# sdr_3157.net
KiCad netlist of a schematic drawn in EAGLE
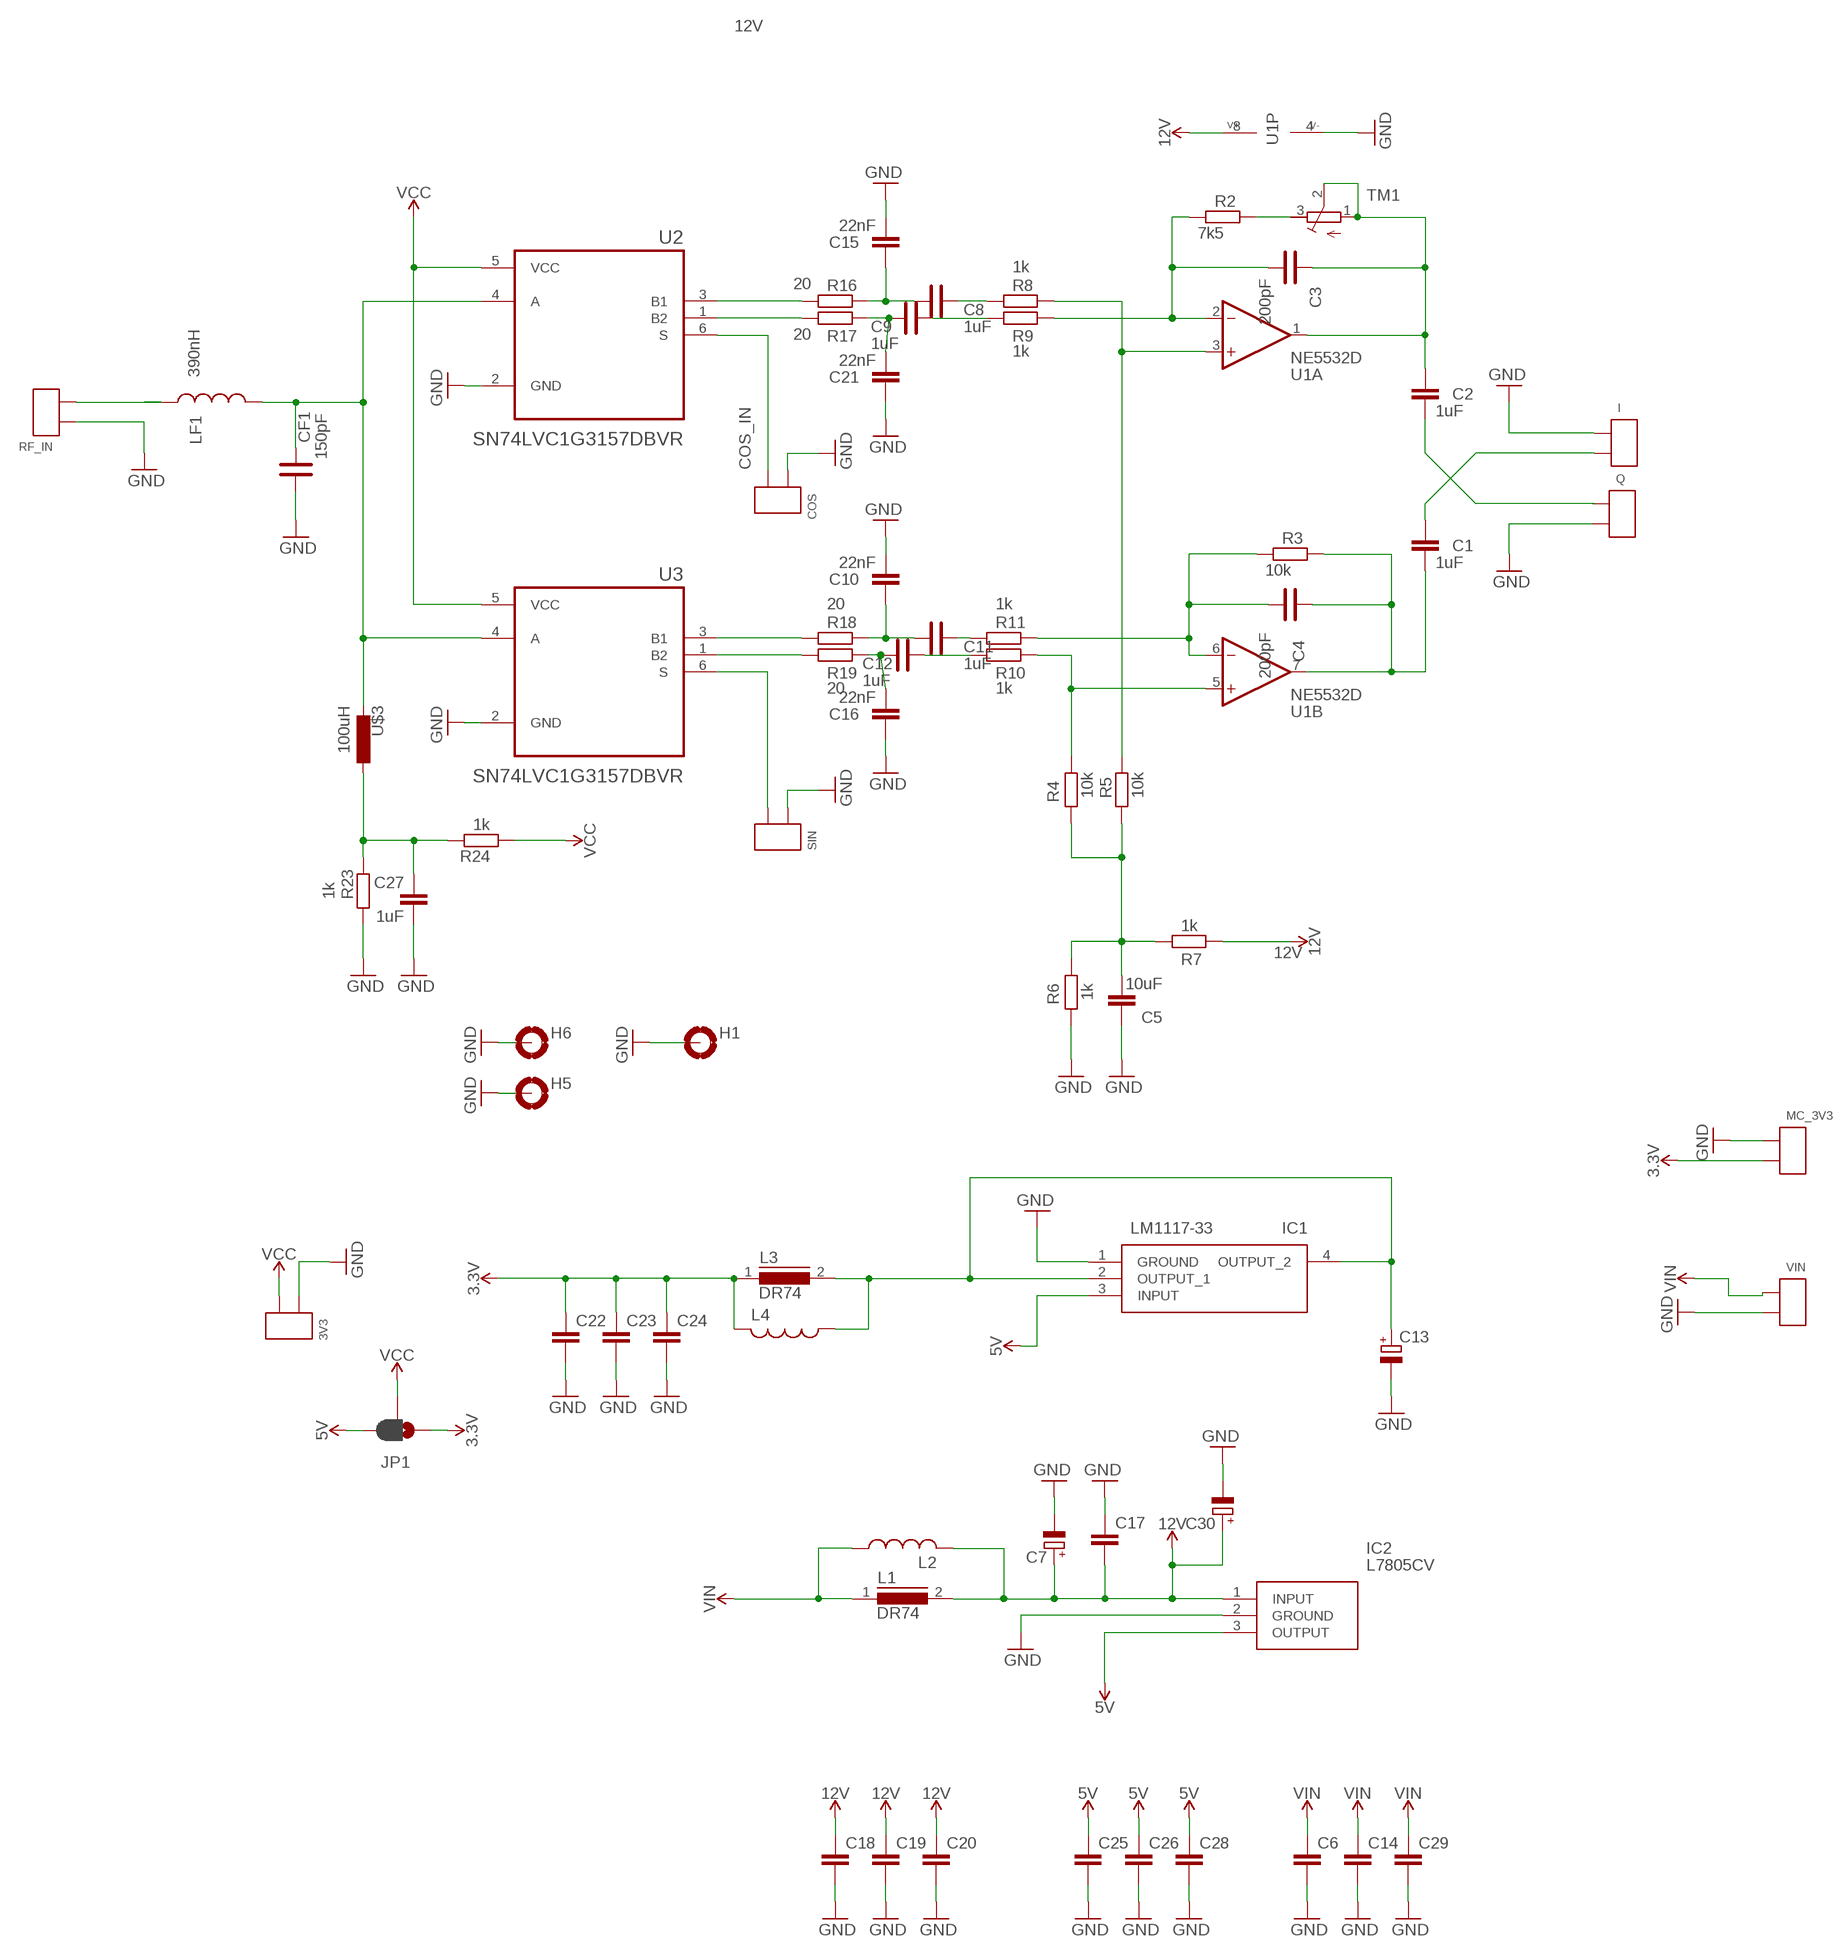
[diagram p0: schematic, sheet 1]

(export (version "E")
  (design (tool "Eeschema 10.0.6"))
  (components
    (comp (ref "3V3")
      (value "2X_SMD_PTH_PIN")
      (footprint "eagle-import:2X_SMD_PTH")
      (libsource (lib "eagle-import") (part "2X_SMD_PTH_PIN"))
    )
    (comp (ref "C1")
      (value "1uF")
      (footprint "eagle-import:C050-045X075")
      (libsource (lib "eagle-import") (part "C-EU050-045X075"))
    )
    (comp (ref "C2")
      (value "1uF")
      (footprint "eagle-import:C050-045X075")
      (libsource (lib "eagle-import") (part "C-EU050-045X075"))
    )
    (comp (ref "C3")
      (value "200pF")
      (footprint "eagle-import:C0805K")
      (libsource (lib "eagle-import") (part "C_0805_PTH"))
    )
    (comp (ref "C4")
      (value "200pF")
      (footprint "eagle-import:C0805K")
      (libsource (lib "eagle-import") (part "C_0805_PTH"))
    )
    (comp (ref "C5")
      (value "10uF")
      (footprint "eagle-import:C0805")
      (libsource (lib "eagle-import") (part "C_0805_SMD"))
    )
    (comp (ref "C6")
      (value "C_0805_SMD")
      (footprint "eagle-import:C0805")
      (libsource (lib "eagle-import") (part "C_0805_SMD"))
    )
    (comp (ref "C7")
      (value "C_POL")
      (footprint "eagle-import:E5-5")
      (libsource (lib "eagle-import") (part "C_POL"))
    )
    (comp (ref "C8")
      (value "1uF")
      (footprint "eagle-import:C0805K")
      (libsource (lib "eagle-import") (part "C_0805_PTH"))
    )
    (comp (ref "C9")
      (value "1uF")
      (footprint "eagle-import:C0805K")
      (libsource (lib "eagle-import") (part "C_0805_PTH"))
    )
    (comp (ref "C10")
      (value "22nF")
      (footprint "eagle-import:C0805")
      (libsource (lib "eagle-import") (part "C_0805_SMD"))
    )
    (comp (ref "C11")
      (value "1uF")
      (footprint "eagle-import:C0805K")
      (libsource (lib "eagle-import") (part "C_0805_PTH"))
    )
    (comp (ref "C12")
      (value "1uF")
      (footprint "eagle-import:C0805K")
      (libsource (lib "eagle-import") (part "C_0805_PTH"))
    )
    (comp (ref "C13")
      (value "C_POL")
      (footprint "eagle-import:E5-5")
      (libsource (lib "eagle-import") (part "C_POL"))
    )
    (comp (ref "C14")
      (value "C_0805_SMD")
      (footprint "eagle-import:C0805")
      (libsource (lib "eagle-import") (part "C_0805_SMD"))
    )
    (comp (ref "C15")
      (value "22nF")
      (footprint "eagle-import:C0805")
      (libsource (lib "eagle-import") (part "C_0805_SMD"))
    )
    (comp (ref "C16")
      (value "22nF")
      (footprint "eagle-import:C0805")
      (libsource (lib "eagle-import") (part "C_0805_SMD"))
    )
    (comp (ref "C17")
      (value "C_0805_SMD")
      (footprint "eagle-import:C0805")
      (libsource (lib "eagle-import") (part "C_0805_SMD"))
    )
    (comp (ref "C18")
      (value "C_0805_SMD")
      (footprint "eagle-import:C0805")
      (libsource (lib "eagle-import") (part "C_0805_SMD"))
    )
    (comp (ref "C19")
      (value "C_0805_SMD")
      (footprint "eagle-import:C0805")
      (libsource (lib "eagle-import") (part "C_0805_SMD"))
    )
    (comp (ref "C20")
      (value "C_0805_SMD")
      (footprint "eagle-import:C0805")
      (libsource (lib "eagle-import") (part "C_0805_SMD"))
    )
    (comp (ref "C21")
      (value "22nF")
      (footprint "eagle-import:C0805")
      (libsource (lib "eagle-import") (part "C_0805_SMD"))
    )
    (comp (ref "C22")
      (value "C_0805_SMD")
      (footprint "eagle-import:C0805")
      (libsource (lib "eagle-import") (part "C_0805_SMD"))
    )
    (comp (ref "C23")
      (value "C_0805_SMD")
      (footprint "eagle-import:C0805")
      (libsource (lib "eagle-import") (part "C_0805_SMD"))
    )
    (comp (ref "C24")
      (value "C_0805_SMD")
      (footprint "eagle-import:C0805")
      (libsource (lib "eagle-import") (part "C_0805_SMD"))
    )
    (comp (ref "C25")
      (value "C_0805_SMD")
      (footprint "eagle-import:C0805")
      (libsource (lib "eagle-import") (part "C_0805_SMD"))
    )
    (comp (ref "C26")
      (value "C_0805_SMD")
      (footprint "eagle-import:C0805")
      (libsource (lib "eagle-import") (part "C_0805_SMD"))
    )
    (comp (ref "C27")
      (value "1uF")
      (footprint "eagle-import:C0805")
      (libsource (lib "eagle-import") (part "C_0805_SMD"))
    )
    (comp (ref "C28")
      (value "C_0805_SMD")
      (footprint "eagle-import:C0805")
      (libsource (lib "eagle-import") (part "C_0805_SMD"))
    )
    (comp (ref "C29")
      (value "C_0805_SMD")
      (footprint "eagle-import:C0805")
      (libsource (lib "eagle-import") (part "C_0805_SMD"))
    )
    (comp (ref "C30")
      (value "C_POL")
      (footprint "eagle-import:E5-5")
      (libsource (lib "eagle-import") (part "C_POL"))
    )
    (comp (ref "CF1")
      (value "150pF")
      (footprint "eagle-import:C0805K")
      (libsource (lib "eagle-import") (part "C_0805_PTH"))
    )
    (comp (ref "COS")
      (value "2X_SMD_PTH_PIN")
      (footprint "eagle-import:2X_SMD_PTH")
      (libsource (lib "eagle-import") (part "2X_SMD_PTH_PIN"))
    )
    (comp (ref "H1")
      (value "MOUNT-PAD-ROUND3.0")
      (footprint "eagle-import:3,0-PAD")
      (libsource (lib "eagle-import") (part "MOUNT-PAD-ROUND3.0"))
    )
    (comp (ref "H5")
      (value "MOUNT-PAD-ROUND3.0")
      (footprint "eagle-import:3,0-PAD")
      (libsource (lib "eagle-import") (part "MOUNT-PAD-ROUND3.0"))
    )
    (comp (ref "H6")
      (value "MOUNT-PAD-ROUND3.0")
      (footprint "eagle-import:3,0-PAD")
      (libsource (lib "eagle-import") (part "MOUNT-PAD-ROUND3.0"))
    )
    (comp (ref "I")
      (value "2X_SMD_PTH_PIN")
      (footprint "eagle-import:2X_SMD_PTH")
      (libsource (lib "eagle-import") (part "2X_SMD_PTH_PIN"))
    )
    (comp (ref "IC1")
      (value "LM1117-33")
      (footprint "eagle-import:SOT230P700X180-4N")
      (fields
        (field (name "ARROW_PART_NUMBER") "LM1117MPX-33NOPB")
        (field (name "MOUSER_PART_NUMBER") "863-LM1117MPX-33NOPB")
      )
      (libsource (lib "eagle-import") (part "LM1117MPX-33NOPB"))
    )
    (comp (ref "IC2")
      (value "L7805CV")
      (footprint "eagle-import:TO255P460X1020X2008-3P")
      (fields (field (name "MOUSER_PART_NUMBER") "511-L7805CV"))
      (libsource (lib "eagle-import") (part "L7805CV"))
    )
    (comp (ref "JP1")
      (value "JUMPER-SMT_3_1-NC_PASTE_NO-SILK")
      (footprint "eagle-import:SMT-JUMPER_3_1-NC_PASTE_NO-SILK")
      (libsource (lib "eagle-import") (part "JUMPER-SMT_3_1-NC_PASTE_NO-SILK"))
    )
    (comp (ref "L1")
      (value "DR74")
      (footprint "eagle-import:DR74")
      (libsource (lib "eagle-import") (part "DR74"))
    )
    (comp (ref "L2")
      (value "L_0805_PTH")
      (footprint "eagle-import:M0805")
      (libsource (lib "eagle-import") (part "L_0805_PTH"))
    )
    (comp (ref "L3")
      (value "DR74")
      (footprint "eagle-import:DR74")
      (libsource (lib "eagle-import") (part "DR74"))
    )
    (comp (ref "L4")
      (value "L_0805_PTH")
      (footprint "eagle-import:M0805")
      (libsource (lib "eagle-import") (part "L_0805_PTH"))
    )
    (comp (ref "LF1")
      (value "390nH")
      (footprint "eagle-import:M0805")
      (libsource (lib "eagle-import") (part "L_0805_PTH"))
    )
    (comp (ref "MC_3V3")
      (value "2X_SMD_PTH_PIN")
      (footprint "eagle-import:2X_SMD_PTH")
      (libsource (lib "eagle-import") (part "2X_SMD_PTH_PIN"))
    )
    (comp (ref "Q")
      (value "2X_SMD_PTH_PIN")
      (footprint "eagle-import:2X_SMD_PTH")
      (libsource (lib "eagle-import") (part "2X_SMD_PTH_PIN"))
    )
    (comp (ref "R2")
      (value "7k5")
      (footprint "eagle-import:R0805W")
      (libsource (lib "eagle-import") (part "R_0805_SMD"))
    )
    (comp (ref "R3")
      (value "10k")
      (footprint "eagle-import:R0805W")
      (libsource (lib "eagle-import") (part "R_0805_SMD"))
    )
    (comp (ref "R4")
      (value "10k")
      (footprint "eagle-import:R0805W")
      (libsource (lib "eagle-import") (part "R_0805_SMD"))
    )
    (comp (ref "R5")
      (value "10k")
      (footprint "eagle-import:R0805W")
      (libsource (lib "eagle-import") (part "R_0805_SMD"))
    )
    (comp (ref "R6")
      (value "1k")
      (footprint "eagle-import:R0805W")
      (libsource (lib "eagle-import") (part "R_0805_SMD"))
    )
    (comp (ref "R7")
      (value "1k")
      (footprint "eagle-import:R0805W")
      (libsource (lib "eagle-import") (part "R_0805_SMD"))
    )
    (comp (ref "R8")
      (value "1k")
      (footprint "eagle-import:R0805W")
      (libsource (lib "eagle-import") (part "R_0805_SMD"))
    )
    (comp (ref "R9")
      (value "1k")
      (footprint "eagle-import:R0805W")
      (libsource (lib "eagle-import") (part "R_0805_SMD"))
    )
    (comp (ref "R10")
      (value "1k")
      (footprint "eagle-import:R0805W")
      (libsource (lib "eagle-import") (part "R_0805_SMD"))
    )
    (comp (ref "R11")
      (value "1k")
      (footprint "eagle-import:R0805W")
      (libsource (lib "eagle-import") (part "R_0805_SMD"))
    )
    (comp (ref "R16")
      (value "20")
      (footprint "eagle-import:R0805W")
      (libsource (lib "eagle-import") (part "R_0805_SMD"))
    )
    (comp (ref "R17")
      (value "20")
      (footprint "eagle-import:R0805W")
      (libsource (lib "eagle-import") (part "R_0805_SMD"))
    )
    (comp (ref "R18")
      (value "20")
      (footprint "eagle-import:R0805W")
      (libsource (lib "eagle-import") (part "R_0805_SMD"))
    )
    (comp (ref "R19")
      (value "20")
      (footprint "eagle-import:R0805W")
      (libsource (lib "eagle-import") (part "R_0805_SMD"))
    )
    (comp (ref "R23")
      (value "1k")
      (footprint "eagle-import:R0805W")
      (libsource (lib "eagle-import") (part "R_0805_SMD"))
    )
    (comp (ref "R24")
      (value "1k")
      (footprint "eagle-import:R0805W")
      (libsource (lib "eagle-import") (part "R_0805_SMD"))
    )
    (comp (ref "RF_IN")
      (value "2X_SMD_PTH_PIN")
      (footprint "eagle-import:2X_SMD_PTH")
      (libsource (lib "eagle-import") (part "2X_SMD_PTH_PIN"))
    )
    (comp (ref "SIN")
      (value "2X_SMD_PTH_PIN")
      (footprint "eagle-import:2X_SMD_PTH")
      (libsource (lib "eagle-import") (part "2X_SMD_PTH_PIN"))
    )
    (comp (ref "TM1")
      (value "5k")
      (footprint "eagle-import:RTRIM3296W")
      (libsource (lib "eagle-import") (part "R-TRIMM3296W"))
    )
    (comp (ref "U$3")
      (value "100uH")
      (footprint "eagle-import:0207_10")
      (libsource (lib "eagle-import") (part "L-EU0207/10"))
    )
    (comp (ref "U1")
      (value "NE5532D")
      (footprint "eagle-import:SO08")
      (libsource (lib "eagle-import") (part "NE5532D"))
    )
    (comp (ref "U2")
      (value "SN74LVC1G3157DBVR")
      (footprint "eagle-import:SOT95P280X145-6N")
      (fields (field (name "MF") "Texas Instruments"))
      (libsource (lib "eagle-import") (part "SN74LVC1G3157DBVR"))
    )
    (comp (ref "U3")
      (value "SN74LVC1G3157DBVR")
      (footprint "eagle-import:SOT95P280X145-6N")
      (fields (field (name "MF") "Texas Instruments"))
      (libsource (lib "eagle-import") (part "SN74LVC1G3157DBVR"))
    )
    (comp (ref "VIN")
      (value "2X_SMD_PTH_PIN")
      (footprint "eagle-import:2X_SMD_PTH")
      (libsource (lib "eagle-import") (part "2X_SMD_PTH_PIN"))
    )
  )
  (nets
    (net (code "1") (name "/COS_IN") (class "Default")
      (node (ref "COS") (pin "P$2") (pinfunction "PIN1_P$2") (pintype "bidirectional"))
      (node (ref "COS") (pin "T$2") (pinfunction "PIN1_T$2") (pintype "bidirectional"))
      (node (ref "U2") (pin "6") (pinfunction "S_6") (pintype "input"))
    )
    (net (code "2") (name "3.3V") (class "Default")
      (node (ref "C22") (pin "1") (pinfunction "1_1") (pintype "passive"))
      (node (ref "C23") (pin "1") (pinfunction "1_1") (pintype "passive"))
      (node (ref "C24") (pin "1") (pinfunction "1_1") (pintype "passive"))
      (node (ref "JP1") (pin "1") (pinfunction "1_1") (pintype "passive"))
      (node (ref "L3") (pin "1") (pinfunction "1_1") (pintype "passive"))
      (node (ref "L4") (pin "2") (pinfunction "2_2") (pintype "passive"))
      (node (ref "L4") (pin "P$2") (pinfunction "2_P$2") (pintype "passive"))
      (node (ref "MC_3V3") (pin "P$2") (pinfunction "PIN1_P$2") (pintype "bidirectional"))
      (node (ref "MC_3V3") (pin "T$2") (pinfunction "PIN1_T$2") (pintype "bidirectional"))
    )
    (net (code "3") (name "5V") (class "Default")
      (node (ref "C25") (pin "1") (pinfunction "1_1") (pintype "passive"))
      (node (ref "C26") (pin "1") (pinfunction "1_1") (pintype "passive"))
      (node (ref "C28") (pin "1") (pinfunction "1_1") (pintype "passive"))
      (node (ref "IC1") (pin "3") (pinfunction "INPUT_3") (pintype "bidirectional"))
      (node (ref "IC2") (pin "3") (pinfunction "OUTPUT_3") (pintype "bidirectional"))
      (node (ref "JP1") (pin "3") (pinfunction "3_3") (pintype "passive"))
    )
    (net (code "4") (name "12V") (class "Default")
      (node (ref "C17") (pin "2") (pinfunction "2_2") (pintype "passive"))
      (node (ref "C18") (pin "1") (pinfunction "1_1") (pintype "passive"))
      (node (ref "C19") (pin "1") (pinfunction "1_1") (pintype "passive"))
      (node (ref "C20") (pin "1") (pinfunction "1_1") (pintype "passive"))
      (node (ref "C30") (pin "+") (pinfunction "+_+") (pintype "passive"))
      (node (ref "C7") (pin "+") (pinfunction "+_+") (pintype "passive"))
      (node (ref "IC2") (pin "1") (pinfunction "INPUT_1") (pintype "bidirectional"))
      (node (ref "L1") (pin "2") (pinfunction "2_2") (pintype "passive"))
      (node (ref "L2") (pin "2") (pinfunction "2_2") (pintype "passive"))
      (node (ref "L2") (pin "P$2") (pinfunction "2_P$2") (pintype "passive"))
      (node (ref "R7") (pin "1") (pinfunction "1_1") (pintype "passive"))
      (node (ref "U1") (pin "8") (pinfunction "V+_8") (pintype "power_in"))
    )
    (net (code "5") (name "GND") (class "Default")
      (node (ref "3V3") (pin "P$1") (pinfunction "PIN0_P$1") (pintype "bidirectional"))
      (node (ref "3V3") (pin "T$1") (pinfunction "PIN0_T$1") (pintype "bidirectional"))
      (node (ref "C10") (pin "2") (pinfunction "2_2") (pintype "passive"))
      (node (ref "C13") (pin "-") (pinfunction "-_-") (pintype "passive"))
      (node (ref "C14") (pin "2") (pinfunction "2_2") (pintype "passive"))
      (node (ref "C15") (pin "2") (pinfunction "2_2") (pintype "passive"))
      (node (ref "C16") (pin "1") (pinfunction "1_1") (pintype "passive"))
      (node (ref "C17") (pin "1") (pinfunction "1_1") (pintype "passive"))
      (node (ref "C18") (pin "2") (pinfunction "2_2") (pintype "passive"))
      (node (ref "C19") (pin "2") (pinfunction "2_2") (pintype "passive"))
      (node (ref "C20") (pin "2") (pinfunction "2_2") (pintype "passive"))
      (node (ref "C21") (pin "1") (pinfunction "1_1") (pintype "passive"))
      (node (ref "C22") (pin "2") (pinfunction "2_2") (pintype "passive"))
      (node (ref "C23") (pin "2") (pinfunction "2_2") (pintype "passive"))
      (node (ref "C24") (pin "2") (pinfunction "2_2") (pintype "passive"))
      (node (ref "C25") (pin "2") (pinfunction "2_2") (pintype "passive"))
      (node (ref "C26") (pin "2") (pinfunction "2_2") (pintype "passive"))
      (node (ref "C27") (pin "1") (pinfunction "1_1") (pintype "passive"))
      (node (ref "C28") (pin "2") (pinfunction "2_2") (pintype "passive"))
      (node (ref "C29") (pin "2") (pinfunction "2_2") (pintype "passive"))
      (node (ref "C30") (pin "-") (pinfunction "-_-") (pintype "passive"))
      (node (ref "C5") (pin "1") (pinfunction "1_1") (pintype "passive"))
      (node (ref "C6") (pin "2") (pinfunction "2_2") (pintype "passive"))
      (node (ref "C7") (pin "-") (pinfunction "-_-") (pintype "passive"))
      (node (ref "CF1") (pin "1") (pinfunction "1_1") (pintype "bidirectional"))
      (node (ref "CF1") (pin "P$1") (pinfunction "1_P$1") (pintype "bidirectional"))
      (node (ref "COS") (pin "P$1") (pinfunction "PIN0_P$1") (pintype "bidirectional"))
      (node (ref "COS") (pin "T$1") (pinfunction "PIN0_T$1") (pintype "bidirectional"))
      (node (ref "H1") (pin "B3,0") (pinfunction "MOUNT_B3,0") (pintype "passive"))
      (node (ref "H5") (pin "B3,0") (pinfunction "MOUNT_B3,0") (pintype "passive"))
      (node (ref "H6") (pin "B3,0") (pinfunction "MOUNT_B3,0") (pintype "passive"))
      (node (ref "I") (pin "P$1") (pinfunction "PIN0_P$1") (pintype "bidirectional"))
      (node (ref "I") (pin "T$1") (pinfunction "PIN0_T$1") (pintype "bidirectional"))
      (node (ref "IC1") (pin "1") (pinfunction "GROUND_1") (pintype "bidirectional"))
      (node (ref "IC2") (pin "2") (pinfunction "GROUND_2") (pintype "bidirectional"))
      (node (ref "MC_3V3") (pin "P$1") (pinfunction "PIN0_P$1") (pintype "bidirectional"))
      (node (ref "MC_3V3") (pin "T$1") (pinfunction "PIN0_T$1") (pintype "bidirectional"))
      (node (ref "Q") (pin "P$2") (pinfunction "PIN1_P$2") (pintype "bidirectional"))
      (node (ref "Q") (pin "T$2") (pinfunction "PIN1_T$2") (pintype "bidirectional"))
      (node (ref "R23") (pin "1") (pinfunction "1_1") (pintype "passive"))
      (node (ref "R6") (pin "1") (pinfunction "1_1") (pintype "passive"))
      (node (ref "RF_IN") (pin "P$1") (pinfunction "PIN0_P$1") (pintype "bidirectional"))
      (node (ref "RF_IN") (pin "T$1") (pinfunction "PIN0_T$1") (pintype "bidirectional"))
      (node (ref "SIN") (pin "P$1") (pinfunction "PIN0_P$1") (pintype "bidirectional"))
      (node (ref "SIN") (pin "T$1") (pinfunction "PIN0_T$1") (pintype "bidirectional"))
      (node (ref "U1") (pin "4") (pinfunction "V-_4") (pintype "power_in"))
      (node (ref "U2") (pin "2") (pinfunction "GND_2") (pintype "power_in"))
      (node (ref "U3") (pin "2") (pinfunction "GND_2") (pintype "power_in"))
      (node (ref "VIN") (pin "P$2") (pinfunction "PIN1_P$2") (pintype "bidirectional"))
      (node (ref "VIN") (pin "T$2") (pinfunction "PIN1_T$2") (pintype "bidirectional"))
    )
    (net (code "6") (name "Net-(C1-Pad1)") (class "Default")
      (node (ref "C1") (pin "1") (pinfunction "1_1") (pintype "passive"))
      (node (ref "I") (pin "P$2") (pinfunction "PIN1_P$2") (pintype "bidirectional"))
      (node (ref "I") (pin "T$2") (pinfunction "PIN1_T$2") (pintype "bidirectional"))
    )
    (net (code "7") (name "Net-(C2-Pad2)") (class "Default")
      (node (ref "C2") (pin "2") (pinfunction "2_2") (pintype "passive"))
      (node (ref "Q") (pin "P$1") (pinfunction "PIN0_P$1") (pintype "bidirectional"))
      (node (ref "Q") (pin "T$1") (pinfunction "PIN0_T$1") (pintype "bidirectional"))
    )
    (net (code "8") (name "Net-(C5-Pad2)") (class "Default")
      (node (ref "C5") (pin "2") (pinfunction "2_2") (pintype "passive"))
      (node (ref "R4") (pin "1") (pinfunction "1_1") (pintype "passive"))
      (node (ref "R5") (pin "1") (pinfunction "1_1") (pintype "passive"))
      (node (ref "R6") (pin "2") (pinfunction "2_2") (pintype "passive"))
      (node (ref "R7") (pin "2") (pinfunction "2_2") (pintype "passive"))
    )
    (net (code "9") (name "Net-(C8-2-PadP$2)") (class "Default")
      (node (ref "C8") (pin "2") (pinfunction "2_2") (pintype "bidirectional"))
      (node (ref "C8") (pin "P$2") (pinfunction "2_P$2") (pintype "bidirectional"))
      (node (ref "R8") (pin "1") (pinfunction "1_1") (pintype "passive"))
    )
    (net (code "10") (name "Net-(C9-2-PadP$2)") (class "Default")
      (node (ref "C9") (pin "2") (pinfunction "2_2") (pintype "bidirectional"))
      (node (ref "C9") (pin "P$2") (pinfunction "2_P$2") (pintype "bidirectional"))
      (node (ref "R9") (pin "1") (pinfunction "1_1") (pintype "passive"))
    )
    (net (code "11") (name "Net-(C10-Pad1)") (class "Default")
      (node (ref "C10") (pin "1") (pinfunction "1_1") (pintype "passive"))
      (node (ref "C11") (pin "1") (pinfunction "1_1") (pintype "bidirectional"))
      (node (ref "C11") (pin "P$1") (pinfunction "1_P$1") (pintype "bidirectional"))
      (node (ref "R18") (pin "2") (pinfunction "2_2") (pintype "passive"))
    )
    (net (code "12") (name "Net-(C11-2-PadP$2)") (class "Default")
      (node (ref "C11") (pin "2") (pinfunction "2_2") (pintype "bidirectional"))
      (node (ref "C11") (pin "P$2") (pinfunction "2_P$2") (pintype "bidirectional"))
      (node (ref "R11") (pin "1") (pinfunction "1_1") (pintype "passive"))
    )
    (net (code "13") (name "Net-(C12-1-PadP$1)") (class "Default")
      (node (ref "C12") (pin "1") (pinfunction "1_1") (pintype "bidirectional"))
      (node (ref "C12") (pin "P$1") (pinfunction "1_P$1") (pintype "bidirectional"))
      (node (ref "C16") (pin "2") (pinfunction "2_2") (pintype "passive"))
      (node (ref "R19") (pin "2") (pinfunction "2_2") (pintype "passive"))
    )
    (net (code "14") (name "Net-(C12-2-PadP$2)") (class "Default")
      (node (ref "C12") (pin "2") (pinfunction "2_2") (pintype "bidirectional"))
      (node (ref "C12") (pin "P$2") (pinfunction "2_P$2") (pintype "bidirectional"))
      (node (ref "R10") (pin "1") (pinfunction "1_1") (pintype "passive"))
    )
    (net (code "15") (name "Net-(C15-Pad1)") (class "Default")
      (node (ref "C15") (pin "1") (pinfunction "1_1") (pintype "passive"))
      (node (ref "C8") (pin "1") (pinfunction "1_1") (pintype "bidirectional"))
      (node (ref "C8") (pin "P$1") (pinfunction "1_P$1") (pintype "bidirectional"))
      (node (ref "R16") (pin "2") (pinfunction "2_2") (pintype "passive"))
    )
    (net (code "16") (name "Net-(C21-Pad2)") (class "Default")
      (node (ref "C21") (pin "2") (pinfunction "2_2") (pintype "passive"))
      (node (ref "C9") (pin "1") (pinfunction "1_1") (pintype "bidirectional"))
      (node (ref "C9") (pin "P$1") (pinfunction "1_P$1") (pintype "bidirectional"))
      (node (ref "R17") (pin "2") (pinfunction "2_2") (pintype "passive"))
    )
    (net (code "17") (name "Net-(C27-Pad2)") (class "Default")
      (node (ref "C27") (pin "2") (pinfunction "2_2") (pintype "passive"))
      (node (ref "R23") (pin "2") (pinfunction "2_2") (pintype "passive"))
      (node (ref "R24") (pin "2") (pinfunction "2_2") (pintype "passive"))
      (node (ref "U$3") (pin "1") (pinfunction "1_1") (pintype "passive"))
    )
    (net (code "18") (name "Net-(IC1-OUTPUT_1)") (class "Default")
      (node (ref "C13") (pin "+") (pinfunction "+_+") (pintype "passive"))
      (node (ref "IC1") (pin "2") (pinfunction "OUTPUT_1_2") (pintype "bidirectional"))
      (node (ref "IC1") (pin "4") (pinfunction "OUTPUT_2_4") (pintype "bidirectional"))
      (node (ref "L3") (pin "2") (pinfunction "2_2") (pintype "passive"))
      (node (ref "L4") (pin "1") (pinfunction "1_1") (pintype "passive"))
      (node (ref "L4") (pin "P$1") (pinfunction "1_P$1") (pintype "passive"))
    )
    (net (code "19") (name "Net-(LF1-1-PadP$1)") (class "Default")
      (node (ref "LF1") (pin "1") (pinfunction "1_1") (pintype "passive"))
      (node (ref "LF1") (pin "P$1") (pinfunction "1_P$1") (pintype "passive"))
      (node (ref "RF_IN") (pin "P$2") (pinfunction "PIN1_P$2") (pintype "bidirectional"))
      (node (ref "RF_IN") (pin "T$2") (pinfunction "PIN1_T$2") (pintype "bidirectional"))
    )
    (net (code "20") (name "Net-(TM1-A)") (class "Default")
      (node (ref "C2") (pin "1") (pinfunction "1_1") (pintype "passive"))
      (node (ref "C3") (pin "2") (pinfunction "2_2") (pintype "bidirectional"))
      (node (ref "C3") (pin "P$2") (pinfunction "2_P$2") (pintype "bidirectional"))
      (node (ref "TM1") (pin "1") (pinfunction "A_1") (pintype "passive"))
      (node (ref "TM1") (pin "2") (pinfunction "S_2") (pintype "passive"))
      (node (ref "U1") (pin "1") (pinfunction "OUT_1") (pintype "output"))
    )
    (net (code "21") (name "Net-(TM1-E)") (class "Default")
      (node (ref "R2") (pin "2") (pinfunction "2_2") (pintype "passive"))
      (node (ref "TM1") (pin "3") (pinfunction "E_3") (pintype "passive"))
    )
    (net (code "22") (name "Net-(U1A-+IN)") (class "Default")
      (node (ref "R5") (pin "2") (pinfunction "2_2") (pintype "passive"))
      (node (ref "R8") (pin "2") (pinfunction "2_2") (pintype "passive"))
      (node (ref "U1") (pin "3") (pinfunction "+IN_3") (pintype "input"))
    )
    (net (code "23") (name "Net-(U1A--IN)") (class "Default")
      (node (ref "C3") (pin "1") (pinfunction "1_1") (pintype "bidirectional"))
      (node (ref "C3") (pin "P$1") (pinfunction "1_P$1") (pintype "bidirectional"))
      (node (ref "R2") (pin "1") (pinfunction "1_1") (pintype "passive"))
      (node (ref "R9") (pin "2") (pinfunction "2_2") (pintype "passive"))
      (node (ref "U1") (pin "2") (pinfunction "-IN_2") (pintype "input"))
    )
    (net (code "24") (name "Net-(U1B-+IN)") (class "Default")
      (node (ref "R10") (pin "2") (pinfunction "2_2") (pintype "passive"))
      (node (ref "R4") (pin "2") (pinfunction "2_2") (pintype "passive"))
      (node (ref "U1") (pin "5") (pinfunction "+IN_5") (pintype "input"))
    )
    (net (code "25") (name "Net-(U1B--IN)") (class "Default")
      (node (ref "C4") (pin "1") (pinfunction "1_1") (pintype "bidirectional"))
      (node (ref "C4") (pin "P$1") (pinfunction "1_P$1") (pintype "bidirectional"))
      (node (ref "R11") (pin "2") (pinfunction "2_2") (pintype "passive"))
      (node (ref "R3") (pin "1") (pinfunction "1_1") (pintype "passive"))
      (node (ref "U1") (pin "6") (pinfunction "-IN_6") (pintype "input"))
    )
    (net (code "26") (name "Net-(U1B-OUT)") (class "Default")
      (node (ref "C1") (pin "2") (pinfunction "2_2") (pintype "passive"))
      (node (ref "C4") (pin "2") (pinfunction "2_2") (pintype "bidirectional"))
      (node (ref "C4") (pin "P$2") (pinfunction "2_P$2") (pintype "bidirectional"))
      (node (ref "R3") (pin "2") (pinfunction "2_2") (pintype "passive"))
      (node (ref "U1") (pin "7") (pinfunction "OUT_7") (pintype "output"))
    )
    (net (code "27") (name "Net-(U2-A)") (class "Default")
      (node (ref "CF1") (pin "2") (pinfunction "2_2") (pintype "bidirectional"))
      (node (ref "CF1") (pin "P$2") (pinfunction "2_P$2") (pintype "bidirectional"))
      (node (ref "LF1") (pin "2") (pinfunction "2_2") (pintype "passive"))
      (node (ref "LF1") (pin "P$2") (pinfunction "2_P$2") (pintype "passive"))
      (node (ref "U$3") (pin "2") (pinfunction "2_2") (pintype "passive"))
      (node (ref "U2") (pin "4") (pinfunction "A_4") (pintype "output"))
      (node (ref "U3") (pin "4") (pinfunction "A_4") (pintype "output"))
    )
    (net (code "28") (name "Net-(U2-B1)") (class "Default")
      (node (ref "R16") (pin "1") (pinfunction "1_1") (pintype "passive"))
      (node (ref "U2") (pin "3") (pinfunction "B1_3") (pintype "input"))
    )
    (net (code "29") (name "Net-(U2-B2)") (class "Default")
      (node (ref "R17") (pin "1") (pinfunction "1_1") (pintype "passive"))
      (node (ref "U2") (pin "1") (pinfunction "B2_1") (pintype "input"))
    )
    (net (code "30") (name "Net-(U3-B1)") (class "Default")
      (node (ref "R18") (pin "1") (pinfunction "1_1") (pintype "passive"))
      (node (ref "U3") (pin "3") (pinfunction "B1_3") (pintype "input"))
    )
    (net (code "31") (name "Net-(U3-B2)") (class "Default")
      (node (ref "R19") (pin "1") (pinfunction "1_1") (pintype "passive"))
      (node (ref "U3") (pin "1") (pinfunction "B2_1") (pintype "input"))
    )
    (net (code "32") (name "Net-(U3-S)") (class "Default")
      (node (ref "SIN") (pin "P$2") (pinfunction "PIN1_P$2") (pintype "bidirectional"))
      (node (ref "SIN") (pin "T$2") (pinfunction "PIN1_T$2") (pintype "bidirectional"))
      (node (ref "U3") (pin "6") (pinfunction "S_6") (pintype "input"))
    )
    (net (code "33") (name "VCC") (class "Default")
      (node (ref "3V3") (pin "P$2") (pinfunction "PIN1_P$2") (pintype "bidirectional"))
      (node (ref "3V3") (pin "T$2") (pinfunction "PIN1_T$2") (pintype "bidirectional"))
      (node (ref "JP1") (pin "2") (pinfunction "2_2") (pintype "passive"))
      (node (ref "R24") (pin "1") (pinfunction "1_1") (pintype "passive"))
      (node (ref "U2") (pin "5") (pinfunction "VCC_5") (pintype "power_in"))
      (node (ref "U3") (pin "5") (pinfunction "VCC_5") (pintype "power_in"))
    )
    (net (code "34") (name "VIN") (class "Default")
      (node (ref "C14") (pin "1") (pinfunction "1_1") (pintype "passive"))
      (node (ref "C29") (pin "1") (pinfunction "1_1") (pintype "passive"))
      (node (ref "C6") (pin "1") (pinfunction "1_1") (pintype "passive"))
      (node (ref "L1") (pin "1") (pinfunction "1_1") (pintype "passive"))
      (node (ref "L2") (pin "1") (pinfunction "1_1") (pintype "passive"))
      (node (ref "L2") (pin "P$1") (pinfunction "1_P$1") (pintype "passive"))
      (node (ref "VIN") (pin "P$1") (pinfunction "PIN0_P$1") (pintype "bidirectional"))
      (node (ref "VIN") (pin "T$1") (pinfunction "PIN0_T$1") (pintype "bidirectional"))
    )
  )
)
